# 06debug.net
KiCad netlist of a schematic drawn in Altium Designer
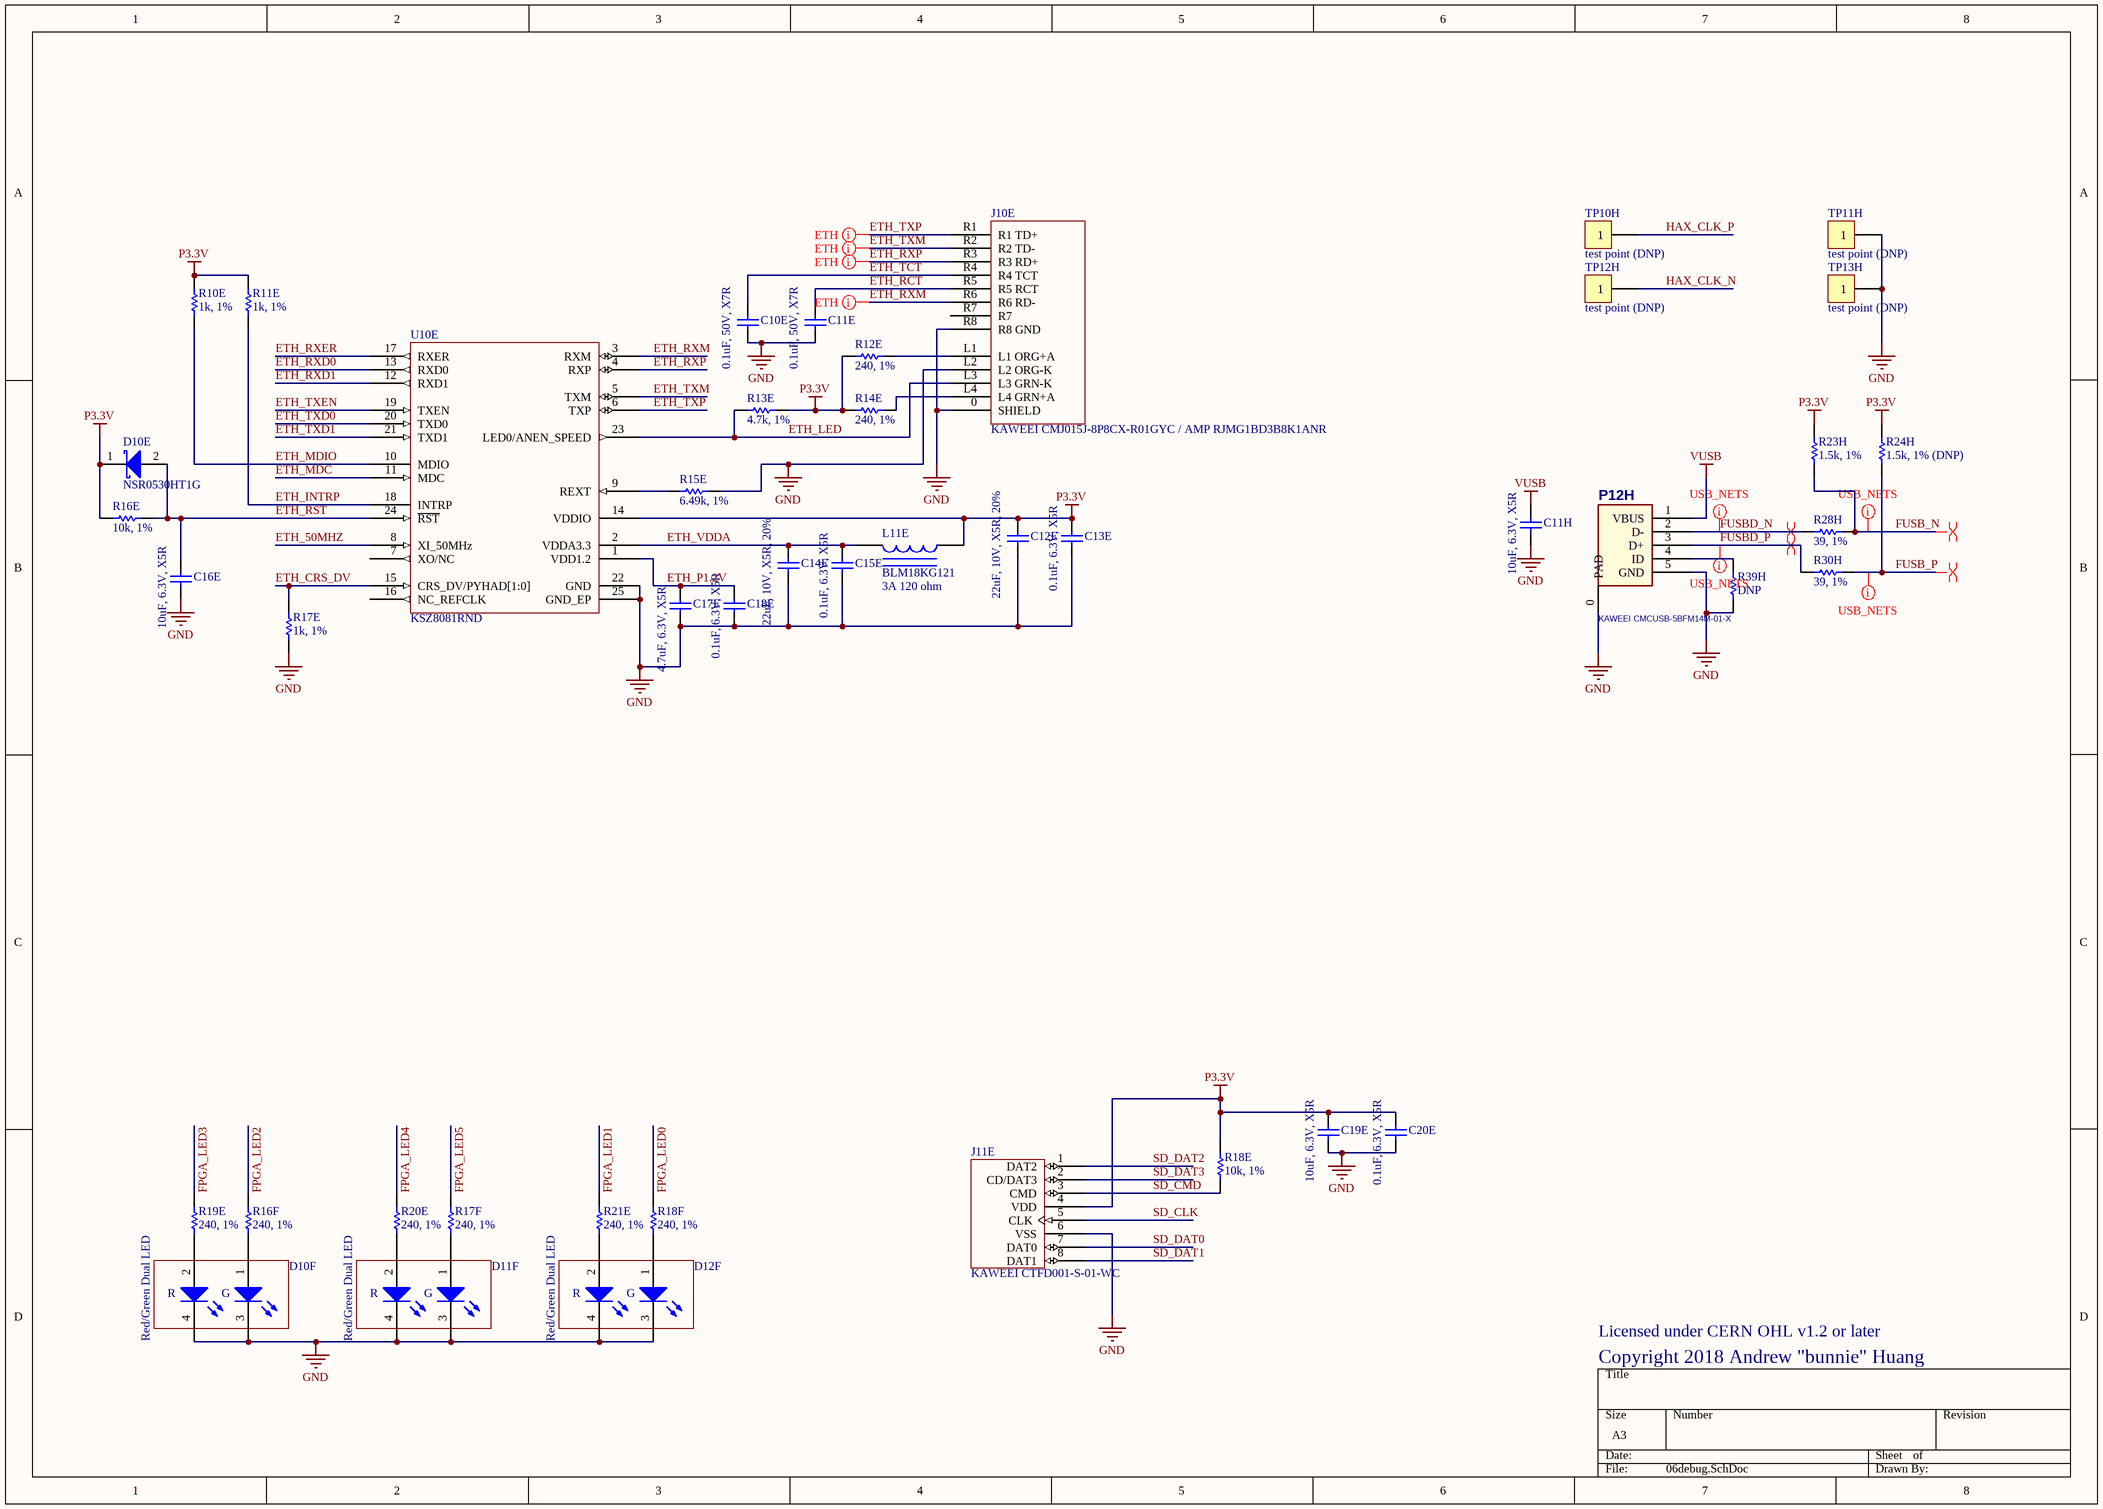
[diagram p0: 06debug.SchDoc]

(export (version "E")
  (design (tool "Eeschema 10.0.6"))
  (components
    (comp (ref "C10E")
      (value "0.1uF, 50V, X7R")
      (footprint "CAPC2012N")
      (description "Capacitor (Semiconductor SIM Model)")
      (fields (field (name "MPN") "CL21B104KBCNNWC"))
      (libsource (lib "Miscellaneous Devices") (part "Cap Semi"))
    )
    (comp (ref "C11E")
      (value "0.1uF, 50V, X7R")
      (footprint "CAPC2012N")
      (description "Capacitor (Semiconductor SIM Model)")
      (fields (field (name "MPN") "CL21B104KBCNNWC"))
      (libsource (lib "Miscellaneous Devices") (part "Cap Semi"))
    )
    (comp (ref "C11H")
      (value "10uF, 6.3V, X5R")
      (footprint "CAPC1608N")
      (description "Capacitor (Semiconductor SIM Model)")
      (fields (field (name "MPN") "CL10A106MQ8NNNC"))
      (libsource (lib "Miscellaneous Devices") (part "Cap Semi"))
    )
    (comp (ref "C12E")
      (value "22uF, 10V, X5R, 20%")
      (footprint "CAPC2012N")
      (description "Capacitor (Semiconductor SIM Model)")
      (fields
        (field (name "MFG") "Murata")
        (field (name "MPN") "GRM21BR61A226ME51L")
        (field (name "PUBLISHER") "Altium Limited")
      )
      (libsource (lib "Miscellaneous Devices") (part "Cap Semi"))
    )
    (comp (ref "C13E")
      (value "0.1uF, 6.3V, X5R")
      (footprint "CAPC0603X03L")
      (description "Capacitor (Semiconductor SIM Model)")
      (fields (field (name "MPN") "CL03A104KQ3NNNC"))
      (libsource (lib "Miscellaneous Devices") (part "Cap Semi"))
    )
    (comp (ref "C14E")
      (value "22uF, 10V, X5R, 20%")
      (footprint "CAPC2012N")
      (description "Capacitor (Semiconductor SIM Model)")
      (fields
        (field (name "MFG") "Murata")
        (field (name "MPN") "GRM21BR61A226ME51L")
        (field (name "PUBLISHER") "Altium Limited")
      )
      (libsource (lib "Miscellaneous Devices") (part "Cap Semi"))
    )
    (comp (ref "C15E")
      (value "0.1uF, 6.3V, X5R")
      (footprint "CAPC0603X03L")
      (description "Capacitor (Semiconductor SIM Model)")
      (fields (field (name "MPN") "CL03A104KQ3NNNC"))
      (libsource (lib "Miscellaneous Devices") (part "Cap Semi"))
    )
    (comp (ref "C16E")
      (value "10uF, 6.3V, X5R")
      (footprint "CAPC1608N")
      (description "Capacitor (Semiconductor SIM Model)")
      (fields (field (name "MPN") "CL10A106MQ8NNNC"))
      (libsource (lib "Miscellaneous Devices") (part "Cap Semi"))
    )
    (comp (ref "C17E")
      (value "4.7uF, 6.3V, X5R")
      (footprint "CAPC1005N")
      (description "Capacitor (Semiconductor SIM Model)")
      (fields (field (name "MPN") "CL05A475MQ5NQNC"))
      (libsource (lib "Miscellaneous Devices") (part "Cap Semi"))
    )
    (comp (ref "C18E")
      (value "0.1uF, 6.3V, X5R")
      (footprint "CAPC0603X03L")
      (description "Capacitor (Semiconductor SIM Model)")
      (fields (field (name "MPN") "CL03A104KQ3NNNC"))
      (libsource (lib "Miscellaneous Devices") (part "Cap Semi"))
    )
    (comp (ref "C19E")
      (value "10uF, 6.3V, X5R")
      (footprint "CAPC1608N")
      (description "Capacitor (Semiconductor SIM Model)")
      (fields (field (name "MPN") "CL10A106MQ8NNNC"))
      (libsource (lib "Miscellaneous Devices") (part "Cap Semi"))
    )
    (comp (ref "C20E")
      (value "0.1uF, 6.3V, X5R")
      (footprint "CAPC0603X03L")
      (description "Capacitor (Semiconductor SIM Model)")
      (fields (field (name "MPN") "CL03A104KQ3NNNC"))
      (libsource (lib "Miscellaneous Devices") (part "Cap Semi"))
    )
    (comp (ref "D10E")
      (value "NSR0530HT1G")
      (footprint "SOD-323")
      (description "Schottky Diode")
      (fields (field (name "MPN") "NSR0530H-D"))
      (libsource (lib "Miscellaneous Devices") (part "D Schottky"))
    )
    (comp (ref "D10F")
      (value "Red/Green Dual LED")
      (footprint "LED_1210_DUAL")
      (description "3.2mm x 2.7mm dual LED red/green")
      (fields (field (name "MPN") "CB-3227QRQGC-PX"))
      (libsource (lib "commonsch-new") (part "DUAL_LED_1210"))
    )
    (comp (ref "D11F")
      (value "Red/Green Dual LED")
      (footprint "LED_1210_DUAL")
      (description "3.2mm x 2.7mm dual LED red/green")
      (fields (field (name "MPN") "CB-3227QRQGC-PX"))
      (libsource (lib "commonsch-new") (part "DUAL_LED_1210"))
    )
    (comp (ref "D12F")
      (value "Red/Green Dual LED")
      (footprint "LED_1210_DUAL")
      (description "3.2mm x 2.7mm dual LED red/green")
      (fields (field (name "MPN") "CB-3227QRQGC-PX"))
      (libsource (lib "commonsch-new") (part "DUAL_LED_1210"))
    )
    (comp (ref "J10E")
      (value "KAWEEI CMJ015J-8P8CX-R01GYC / AMP RJMG1BD3B8K1ANR")
      (footprint "UDE_RB1-125BAG1A")
      (description "10/100 Ethernet Jack with Magnetics")
      (fields (field (name "MPN") "CMJ015J-8P8CX-R01GYC / RJMG1BD3B8K1ANR"))
      (libsource (lib "commonsch-new") (part "UDE RB1-ZZ-0025"))
    )
    (comp (ref "J11E")
      (value "KAWEEI CTFD001-S-01-WC")
      (footprint "AUK_TFC08W01-HC-H")
      (description "Captive Micro-SD card for firmware images")
      (fields (field (name "MPN") "CTFD001-S-01-WC"))
      (libsource (lib "commonsch") (part "MICRO_SD"))
    )
    (comp (ref "L11E")
      (value "BLM18KG121")
      (footprint "INDC1608AN")
      (description "Magnetic-Core Inductor")
      (fields
        (field (name "ALTIUM_VALUE") "3A 120 ohm")
        (field (name "MPN") "BLM18KG121TN1D")
        (field (name "PUBLISHER") "Altium Limited")
      )
      (libsource (lib "Miscellaneous Devices") (part "Inductor Iron"))
    )
    (comp (ref "P12H")
      (value "KAWEEI CMCUSB-5BFM14M-01-X")
      (footprint "USB_MICRO_B_SMT - KAWEEI")
      (description "Micro USB B type connector")
      (fields (field (name "MPN") "CMCUSB-5BFM14M-01-X"))
      (libsource (lib "*") (part "USB_MINI-AB_1"))
    )
    (comp (ref "R10E")
      (value "1k, 1%")
      (footprint "RESC1005N")
      (description "Resistor")
      (fields (field (name "MPN") "RS02U102FT"))
      (libsource (lib "Miscellaneous Devices") (part "Res1"))
    )
    (comp (ref "R11E")
      (value "1k, 1%")
      (footprint "RESC1005N")
      (description "Resistor")
      (fields (field (name "MPN") "RS02U102FT"))
      (libsource (lib "Miscellaneous Devices") (part "Res1"))
    )
    (comp (ref "R12E")
      (value "240, 1%")
      (footprint "CAPC0603X03L")
      (description "Resistor")
      (fields (field (name "MPN") "ANY"))
      (libsource (lib "Miscellaneous Devices") (part "Res1"))
    )
    (comp (ref "R13E")
      (value "4.7k, 1%")
      (footprint "RESC1005N")
      (description "Resistor")
      (fields (field (name "MPN") "ANY"))
      (libsource (lib "Miscellaneous Devices") (part "Res1"))
    )
    (comp (ref "R14E")
      (value "240, 1%")
      (footprint "CAPC0603X03L")
      (description "Resistor")
      (fields (field (name "MPN") "ANY"))
      (libsource (lib "Miscellaneous Devices") (part "Res1"))
    )
    (comp (ref "R15E")
      (value "6.49k, 1%")
      (footprint "RESC1005N")
      (description "Resistor")
      (fields (field (name "MPN") "ANY"))
      (libsource (lib "Miscellaneous Devices") (part "Res1"))
    )
    (comp (ref "R16E")
      (value "10k, 1%")
      (footprint "RESC1005N")
      (description "Resistor")
      (fields (field (name "MPN") "RS02U103FT"))
      (libsource (lib "Miscellaneous Devices") (part "Res1"))
    )
    (comp (ref "R16F")
      (value "240, 1%")
      (footprint "CAPC0603X03L")
      (description "Resistor")
      (fields (field (name "MPN") "ANY"))
      (libsource (lib "Miscellaneous Devices") (part "Res1"))
    )
    (comp (ref "R17E")
      (value "1k, 1%")
      (footprint "RESC1005N")
      (description "Resistor")
      (fields (field (name "MPN") "RS02U102FT"))
      (libsource (lib "Miscellaneous Devices") (part "Res1"))
    )
    (comp (ref "R17F")
      (value "240, 1%")
      (footprint "CAPC0603X03L")
      (description "Resistor")
      (fields (field (name "MPN") "ANY"))
      (libsource (lib "Miscellaneous Devices") (part "Res1"))
    )
    (comp (ref "R18E")
      (value "10k, 1%")
      (footprint "RESC1005N")
      (description "Resistor")
      (fields (field (name "MPN") "RS02U103FT"))
      (libsource (lib "Miscellaneous Devices") (part "Res1"))
    )
    (comp (ref "R18F")
      (value "240, 1%")
      (footprint "CAPC0603X03L")
      (description "Resistor")
      (fields (field (name "MPN") "ANY"))
      (libsource (lib "Miscellaneous Devices") (part "Res1"))
    )
    (comp (ref "R19E")
      (value "240, 1%")
      (footprint "CAPC0603X03L")
      (description "Resistor")
      (fields (field (name "MPN") "ANY"))
      (libsource (lib "Miscellaneous Devices") (part "Res1"))
    )
    (comp (ref "R20E")
      (value "240, 1%")
      (footprint "CAPC0603X03L")
      (description "Resistor")
      (fields (field (name "MPN") "ANY"))
      (libsource (lib "Miscellaneous Devices") (part "Res1"))
    )
    (comp (ref "R21E")
      (value "240, 1%")
      (footprint "CAPC0603X03L")
      (description "Resistor")
      (fields (field (name "MPN") "ANY"))
      (libsource (lib "Miscellaneous Devices") (part "Res1"))
    )
    (comp (ref "R23H")
      (value "1.5k, 1%")
      (footprint "RESC1005N")
      (description "Resistor")
      (fields (field (name "MPN") "RS02U152FT"))
      (libsource (lib "Miscellaneous Devices") (part "Res1"))
    )
    (comp (ref "R24H")
      (value "1.5k, 1% (DNP)")
      (footprint "RESC1005N")
      (description "Resistor")
      (fields (field (name "MPN") "DNP"))
      (libsource (lib "Miscellaneous Devices") (part "Res1"))
    )
    (comp (ref "R28H")
      (value "39, 1%")
      (footprint "RESC1005N")
      (description "Resistor")
      (fields (field (name "MPN") "ANY"))
      (libsource (lib "Miscellaneous Devices") (part "Res1"))
    )
    (comp (ref "R30H")
      (value "39, 1%")
      (footprint "RESC1005N")
      (description "Resistor")
      (fields (field (name "MPN") "ANY"))
      (libsource (lib "Miscellaneous Devices") (part "Res1"))
    )
    (comp (ref "R39H")
      (value "DNP")
      (footprint "RESC1005N")
      (description "Resistor")
      (fields (field (name "MPN") "ANY"))
      (libsource (lib "Miscellaneous Devices") (part "Res1"))
    )
    (comp (ref "TP10H")
      (value "test point (DNP)")
      (footprint "TP_2MM_SQ")
      (description "Connector")
      (libsource (lib "*") (part "CON1"))
    )
    (comp (ref "TP11H")
      (value "test point (DNP)")
      (footprint "TP_2MM_SQ")
      (description "Connector")
      (libsource (lib "*") (part "CON1"))
    )
    (comp (ref "TP12H")
      (value "test point (DNP)")
      (footprint "TP_2MM_SQ")
      (description "Connector")
      (libsource (lib "*") (part "CON1"))
    )
    (comp (ref "TP13H")
      (value "test point (DNP)")
      (footprint "TP_2MM_SQ")
      (description "Connector")
      (libsource (lib "*") (part "CON1"))
    )
    (comp (ref "U10E")
      (value "KSZ8081RND")
      (footprint "QFN50P400X400-24VBN")
      (description "KSZ8081RND MII Ethernet PHY")
      (fields (field (name "MPN") "KSZ8081RNDCA"))
      (libsource (lib "commonsch-new") (part "KSZ8081RND"))
    )
  )
  (nets
    (net (code "1") (name "/ETH_50MHZ") (class "Default")
      (node (ref "U10E") (pin "8") (pinfunction "XI_50MHz_8") (pintype "input"))
    )
    (net (code "2") (name "/ETH_CRS_DV") (class "Default")
      (node (ref "R17E") (pin "2") (pinfunction "2_2") (pintype "passive"))
      (node (ref "U10E") (pin "15") (pinfunction "CRS_DV/PYHAD[1:0]_15") (pintype "input"))
    )
    (net (code "3") (name "/ETH_INTRP") (class "Default")
      (node (ref "R11E") (pin "1") (pinfunction "1_1") (pintype "passive"))
      (node (ref "U10E") (pin "18") (pinfunction "INTRP_18") (pintype "open_collector"))
    )
    (net (code "4") (name "/ETH_LED") (class "Default")
      (node (ref "J10E") (pin "L3") (pinfunction "L3_GRN-K_L3") (pintype "passive"))
      (node (ref "R13E") (pin "2") (pinfunction "2_2") (pintype "passive"))
      (node (ref "U10E") (pin "23") (pinfunction "LED0/ANEN_SPEED_23") (pintype "output"))
    )
    (net (code "5") (name "/ETH_MDC") (class "Default")
      (node (ref "U10E") (pin "11") (pinfunction "MDC_11") (pintype "input"))
    )
    (net (code "6") (name "/ETH_MDIO") (class "Default")
      (node (ref "R10E") (pin "1") (pinfunction "1_1") (pintype "passive"))
      (node (ref "U10E") (pin "10") (pinfunction "MDIO_10") (pintype "open_collector"))
    )
    (net (code "7") (name "/ETH_P1.2V") (class "Default")
      (node (ref "C17E") (pin "1") (pinfunction "1_1") (pintype "passive"))
      (node (ref "C18E") (pin "1") (pinfunction "1_1") (pintype "passive"))
      (node (ref "U10E") (pin "1") (pinfunction "VDD1.2_1") (pintype "power_in"))
    )
    (net (code "8") (name "/ETH_RCT") (class "Default")
      (node (ref "C11E") (pin "1") (pinfunction "1_1") (pintype "passive"))
      (node (ref "J10E") (pin "R5") (pinfunction "R5_RCT_R5") (pintype "passive"))
    )
    (net (code "9") (name "/ETH_RST") (class "Default")
      (node (ref "C16E") (pin "1") (pinfunction "1_1") (pintype "passive"))
      (node (ref "D10E") (pin "2") (pinfunction "A_2") (pintype "passive"))
      (node (ref "R16E") (pin "2") (pinfunction "2_2") (pintype "passive"))
      (node (ref "U10E") (pin "24") (pinfunction "~{RST}_24") (pintype "input"))
    )
    (net (code "10") (name "/ETH_RXD0") (class "Default")
      (node (ref "U10E") (pin "13") (pinfunction "RXD0_13") (pintype "output"))
    )
    (net (code "11") (name "/ETH_RXD1") (class "Default")
      (node (ref "U10E") (pin "12") (pinfunction "RXD1_12") (pintype "output"))
    )
    (net (code "12") (name "/ETH_RXER") (class "Default")
      (node (ref "U10E") (pin "17") (pinfunction "RXER_17") (pintype "output"))
    )
    (net (code "13") (name "/ETH_RXM") (class "Default")
      (node (ref "J10E") (pin "R6") (pinfunction "R6_RD-_R6") (pintype "passive"))
      (node (ref "U10E") (pin "3") (pinfunction "RXM_3") (pintype "bidirectional"))
    )
    (net (code "14") (name "/ETH_RXP") (class "Default")
      (node (ref "J10E") (pin "R3") (pinfunction "R3_RD+_R3") (pintype "passive"))
      (node (ref "U10E") (pin "4") (pinfunction "RXP_4") (pintype "bidirectional"))
    )
    (net (code "15") (name "/ETH_TCT") (class "Default")
      (node (ref "C10E") (pin "1") (pinfunction "1_1") (pintype "passive"))
      (node (ref "J10E") (pin "R4") (pinfunction "R4_TCT_R4") (pintype "passive"))
    )
    (net (code "16") (name "/ETH_TXD0") (class "Default")
      (node (ref "U10E") (pin "20") (pinfunction "TXD0_20") (pintype "input"))
    )
    (net (code "17") (name "/ETH_TXD1") (class "Default")
      (node (ref "U10E") (pin "21") (pinfunction "TXD1_21") (pintype "input"))
    )
    (net (code "18") (name "/ETH_TXEN") (class "Default")
      (node (ref "U10E") (pin "19") (pinfunction "TXEN_19") (pintype "input"))
    )
    (net (code "19") (name "/ETH_TXM") (class "Default")
      (node (ref "J10E") (pin "R2") (pinfunction "R2_TD-_R2") (pintype "passive"))
      (node (ref "U10E") (pin "5") (pinfunction "TXM_5") (pintype "bidirectional"))
    )
    (net (code "20") (name "/ETH_TXP") (class "Default")
      (node (ref "J10E") (pin "R1") (pinfunction "R1_TD+_R1") (pintype "passive"))
      (node (ref "U10E") (pin "6") (pinfunction "TXP_6") (pintype "bidirectional"))
    )
    (net (code "21") (name "/ETH_VDDA") (class "Default")
      (node (ref "C14E") (pin "1") (pinfunction "1_1") (pintype "passive"))
      (node (ref "C15E") (pin "1") (pinfunction "1_1") (pintype "passive"))
      (node (ref "L11E") (pin "2") (pinfunction "2_2") (pintype "passive"))
      (node (ref "U10E") (pin "2") (pinfunction "VDDA3.3_2") (pintype "power_in"))
    )
    (net (code "22") (name "/FPGA_LED0") (class "Default")
      (node (ref "R18F") (pin "2") (pinfunction "2_2") (pintype "passive"))
    )
    (net (code "23") (name "/FPGA_LED1") (class "Default")
      (node (ref "R21E") (pin "2") (pinfunction "2_2") (pintype "passive"))
    )
    (net (code "24") (name "/FPGA_LED2") (class "Default")
      (node (ref "R16F") (pin "2") (pinfunction "2_2") (pintype "passive"))
    )
    (net (code "25") (name "/FPGA_LED3") (class "Default")
      (node (ref "R19E") (pin "2") (pinfunction "2_2") (pintype "passive"))
    )
    (net (code "26") (name "/FPGA_LED4") (class "Default")
      (node (ref "R20E") (pin "2") (pinfunction "2_2") (pintype "passive"))
    )
    (net (code "27") (name "/FPGA_LED5") (class "Default")
      (node (ref "R17F") (pin "2") (pinfunction "2_2") (pintype "passive"))
    )
    (net (code "28") (name "/FUSBD_N") (class "Default")
      (node (ref "P12H") (pin "2") (pinfunction "D-_2") (pintype "passive"))
      (node (ref "R28H") (pin "2") (pinfunction "2_2") (pintype "passive"))
    )
    (net (code "29") (name "/FUSBD_P") (class "Default")
      (node (ref "P12H") (pin "3") (pinfunction "D+_3") (pintype "passive"))
      (node (ref "R30H") (pin "2") (pinfunction "2_2") (pintype "passive"))
    )
    (net (code "30") (name "/FUSB_N") (class "Default")
      (node (ref "R23H") (pin "2") (pinfunction "2_2") (pintype "passive"))
      (node (ref "R28H") (pin "1") (pinfunction "1_1") (pintype "passive"))
    )
    (net (code "31") (name "/FUSB_P") (class "Default")
      (node (ref "R24H") (pin "2") (pinfunction "2_2") (pintype "passive"))
      (node (ref "R30H") (pin "1") (pinfunction "1_1") (pintype "passive"))
    )
    (net (code "32") (name "/HAX_CLK_N") (class "Default")
      (node (ref "TP12H") (pin "1") (pinfunction "1_1") (pintype "passive"))
    )
    (net (code "33") (name "/HAX_CLK_P") (class "Default")
      (node (ref "TP10H") (pin "1") (pinfunction "1_1") (pintype "passive"))
    )
    (net (code "34") (name "/SD_CLK") (class "Default")
      (node (ref "J11E") (pin "5") (pinfunction "CLK_5") (pintype "input"))
    )
    (net (code "35") (name "/SD_CMD") (class "Default")
      (node (ref "J11E") (pin "3") (pinfunction "CMD_3") (pintype "bidirectional"))
      (node (ref "R18E") (pin "2") (pinfunction "2_2") (pintype "passive"))
    )
    (net (code "36") (name "/SD_DAT0") (class "Default")
      (node (ref "J11E") (pin "7") (pinfunction "DAT0_7") (pintype "bidirectional"))
    )
    (net (code "37") (name "/SD_DAT1") (class "Default")
      (node (ref "J11E") (pin "8") (pinfunction "DAT1_8") (pintype "bidirectional"))
    )
    (net (code "38") (name "/SD_DAT2") (class "Default")
      (node (ref "J11E") (pin "1") (pinfunction "DAT2_1") (pintype "bidirectional"))
    )
    (net (code "39") (name "/SD_DAT3") (class "Default")
      (node (ref "J11E") (pin "2") (pinfunction "CD/DAT3_2") (pintype "bidirectional"))
    )
    (net (code "40") (name "GND") (class "Default")
      (node (ref "C10E") (pin "2") (pinfunction "2_2") (pintype "passive"))
      (node (ref "C11E") (pin "2") (pinfunction "2_2") (pintype "passive"))
      (node (ref "C11H") (pin "2") (pinfunction "2_2") (pintype "passive"))
      (node (ref "C12E") (pin "2") (pinfunction "2_2") (pintype "passive"))
      (node (ref "C13E") (pin "2") (pinfunction "2_2") (pintype "passive"))
      (node (ref "C14E") (pin "2") (pinfunction "2_2") (pintype "passive"))
      (node (ref "C15E") (pin "2") (pinfunction "2_2") (pintype "passive"))
      (node (ref "C16E") (pin "2") (pinfunction "2_2") (pintype "passive"))
      (node (ref "C17E") (pin "2") (pinfunction "2_2") (pintype "passive"))
      (node (ref "C18E") (pin "2") (pinfunction "2_2") (pintype "passive"))
      (node (ref "C19E") (pin "2") (pinfunction "2_2") (pintype "passive"))
      (node (ref "C20E") (pin "2") (pinfunction "2_2") (pintype "passive"))
      (node (ref "D10F") (pin "3") (pinfunction "K_3") (pintype "passive"))
      (node (ref "D10F") (pin "4") (pinfunction "K_4") (pintype "passive"))
      (node (ref "D11F") (pin "3") (pinfunction "K_3") (pintype "passive"))
      (node (ref "D11F") (pin "4") (pinfunction "K_4") (pintype "passive"))
      (node (ref "D12F") (pin "3") (pinfunction "K_3") (pintype "passive"))
      (node (ref "D12F") (pin "4") (pinfunction "K_4") (pintype "passive"))
      (node (ref "J10E") (pin "0") (pinfunction "SHIELD_0") (pintype "passive"))
      (node (ref "J10E") (pin "L2") (pinfunction "L2_ORG-K_L2") (pintype "passive"))
      (node (ref "J10E") (pin "R8") (pinfunction "R8_GND_R8") (pintype "passive"))
      (node (ref "J11E") (pin "6") (pinfunction "VSS_6") (pintype "power_in"))
      (node (ref "P12H") (pin "0") (pinfunction "PAD_0") (pintype "passive"))
      (node (ref "P12H") (pin "5") (pinfunction "GND_5") (pintype "passive"))
      (node (ref "R15E") (pin "1") (pinfunction "1_1") (pintype "passive"))
      (node (ref "R17E") (pin "1") (pinfunction "1_1") (pintype "passive"))
      (node (ref "R39H") (pin "2") (pinfunction "2_2") (pintype "passive"))
      (node (ref "TP11H") (pin "1") (pinfunction "1_1") (pintype "passive"))
      (node (ref "TP13H") (pin "1") (pinfunction "1_1") (pintype "passive"))
      (node (ref "U10E") (pin "22") (pinfunction "GND_22") (pintype "power_in"))
      (node (ref "U10E") (pin "25") (pinfunction "GND_EP_25") (pintype "power_in"))
    )
    (net (code "41") (name "Net-(D10F-A-Pad1)") (class "Default")
      (node (ref "D10F") (pin "1") (pinfunction "A_1") (pintype "passive"))
      (node (ref "R16F") (pin "1") (pinfunction "1_1") (pintype "passive"))
    )
    (net (code "42") (name "Net-(D10F-A-Pad2)") (class "Default")
      (node (ref "D10F") (pin "2") (pinfunction "A_2") (pintype "passive"))
      (node (ref "R19E") (pin "1") (pinfunction "1_1") (pintype "passive"))
    )
    (net (code "43") (name "Net-(D11F-A-Pad1)") (class "Default")
      (node (ref "D11F") (pin "1") (pinfunction "A_1") (pintype "passive"))
      (node (ref "R17F") (pin "1") (pinfunction "1_1") (pintype "passive"))
    )
    (net (code "44") (name "Net-(D11F-A-Pad2)") (class "Default")
      (node (ref "D11F") (pin "2") (pinfunction "A_2") (pintype "passive"))
      (node (ref "R20E") (pin "1") (pinfunction "1_1") (pintype "passive"))
    )
    (net (code "45") (name "Net-(D12F-A-Pad1)") (class "Default")
      (node (ref "D12F") (pin "1") (pinfunction "A_1") (pintype "passive"))
      (node (ref "R18F") (pin "1") (pinfunction "1_1") (pintype "passive"))
    )
    (net (code "46") (name "Net-(D12F-A-Pad2)") (class "Default")
      (node (ref "D12F") (pin "2") (pinfunction "A_2") (pintype "passive"))
      (node (ref "R21E") (pin "1") (pinfunction "1_1") (pintype "passive"))
    )
    (net (code "47") (name "Net-(J10E-L1_ORG+A)") (class "Default")
      (node (ref "J10E") (pin "L1") (pinfunction "L1_ORG+A_L1") (pintype "passive"))
      (node (ref "R12E") (pin "1") (pinfunction "1_1") (pintype "passive"))
    )
    (net (code "48") (name "Net-(J10E-L4_GRN+A)") (class "Default")
      (node (ref "J10E") (pin "L4") (pinfunction "L4_GRN+A_L4") (pintype "passive"))
      (node (ref "R14E") (pin "1") (pinfunction "1_1") (pintype "passive"))
    )
    (net (code "49") (name "Net-(P12H-ID)") (class "Default")
      (node (ref "P12H") (pin "4") (pinfunction "ID_4") (pintype "passive"))
      (node (ref "R39H") (pin "1") (pinfunction "1_1") (pintype "passive"))
    )
    (net (code "50") (name "Net-(U10E-REXT)") (class "Default")
      (node (ref "R15E") (pin "2") (pinfunction "2_2") (pintype "passive"))
      (node (ref "U10E") (pin "9") (pinfunction "REXT_9") (pintype "input"))
    )
    (net (code "51") (name "P3.3V") (class "Default")
      (node (ref "C12E") (pin "1") (pinfunction "1_1") (pintype "passive"))
      (node (ref "C13E") (pin "1") (pinfunction "1_1") (pintype "passive"))
      (node (ref "C19E") (pin "1") (pinfunction "1_1") (pintype "passive"))
      (node (ref "C20E") (pin "1") (pinfunction "1_1") (pintype "passive"))
      (node (ref "D10E") (pin "1") (pinfunction "K_1") (pintype "passive"))
      (node (ref "J11E") (pin "4") (pinfunction "VDD_4") (pintype "power_in"))
      (node (ref "L11E") (pin "1") (pinfunction "1_1") (pintype "passive"))
      (node (ref "R10E") (pin "2") (pinfunction "2_2") (pintype "passive"))
      (node (ref "R11E") (pin "2") (pinfunction "2_2") (pintype "passive"))
      (node (ref "R12E") (pin "2") (pinfunction "2_2") (pintype "passive"))
      (node (ref "R13E") (pin "1") (pinfunction "1_1") (pintype "passive"))
      (node (ref "R14E") (pin "2") (pinfunction "2_2") (pintype "passive"))
      (node (ref "R16E") (pin "1") (pinfunction "1_1") (pintype "passive"))
      (node (ref "R18E") (pin "1") (pinfunction "1_1") (pintype "passive"))
      (node (ref "R23H") (pin "1") (pinfunction "1_1") (pintype "passive"))
      (node (ref "R24H") (pin "1") (pinfunction "1_1") (pintype "passive"))
      (node (ref "U10E") (pin "14") (pinfunction "VDDIO_14") (pintype "power_in"))
    )
    (net (code "52") (name "VUSB") (class "Default")
      (node (ref "C11H") (pin "1") (pinfunction "1_1") (pintype "passive"))
      (node (ref "P12H") (pin "1") (pinfunction "VBUS_1") (pintype "passive"))
    )
    (net (code "53") (name "unconnected-(J10E-PadR7)") (class "Default")
      (node (ref "J10E") (pin "R7") (pinfunction "R7_R7") (pintype "passive"))
    )
    (net (code "54") (name "unconnected-(U10E-NC_REFCLK-Pad16)") (class "Default")
      (node (ref "U10E") (pin "16") (pinfunction "NC_REFCLK_16") (pintype "output"))
    )
    (net (code "55") (name "unconnected-(U10E-XO{slash}NC-Pad7)") (class "Default")
      (node (ref "U10E") (pin "7") (pinfunction "XO/NC_7") (pintype "output"))
    )
  )
)
